# motor-control.net
KiCad netlist of a schematic drawn in Altium Designer
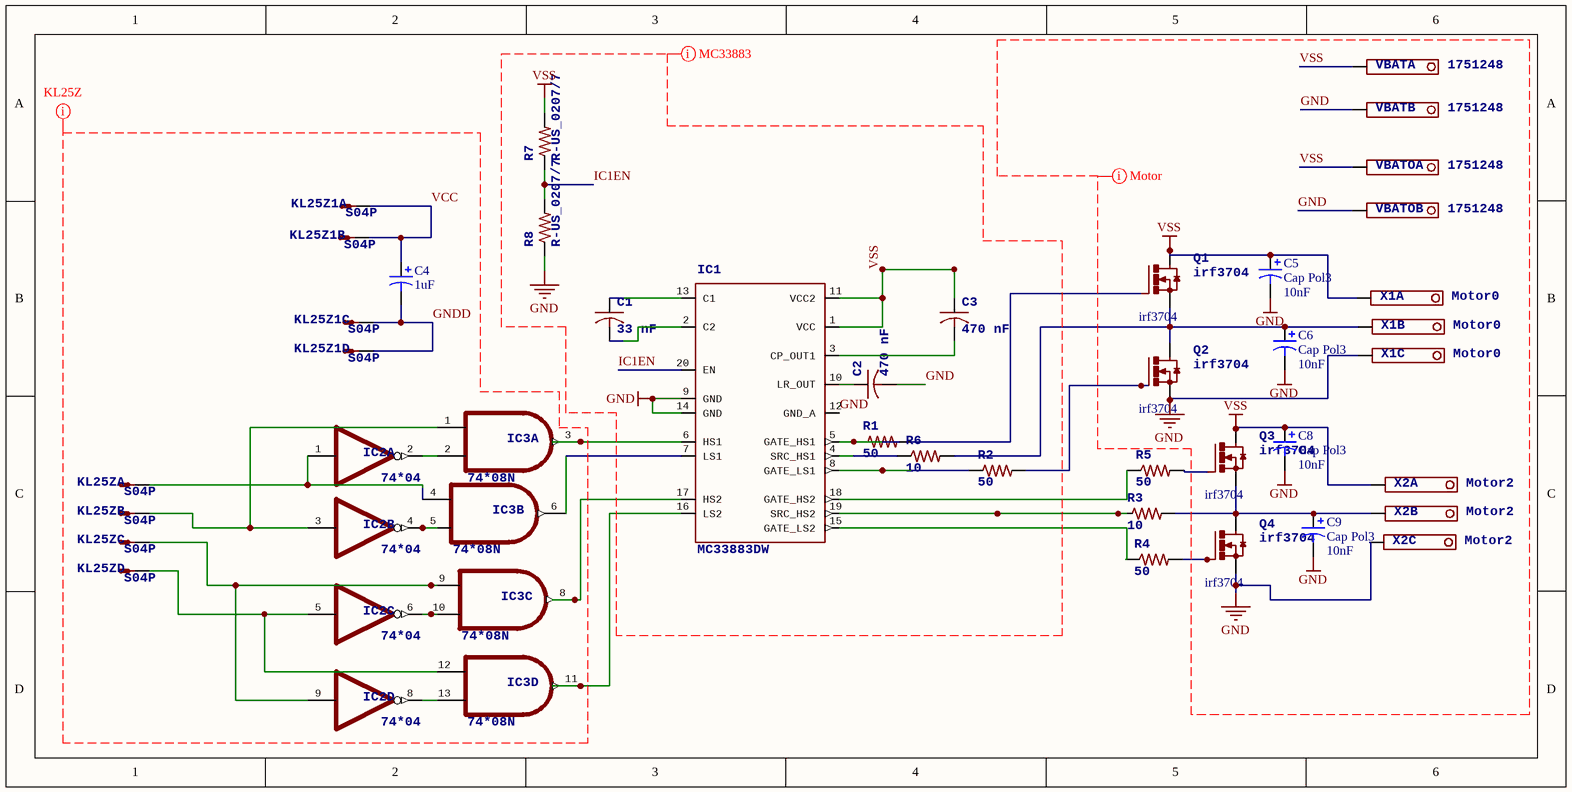
[diagram p0: motor-control.SchDoc]

(export (version "E")
  (design (tool "Eeschema 10.0.6"))
  (components
    (comp (ref "C1")
      (value "33 nF")
      (footprint "C0805")
      (description "<B>CAPACITOR</B>, American symbol")
      (libsource (lib "adafruit") (part "C-USC0805"))
    )
    (comp (ref "C2")
      (value "470 nF")
      (footprint "C0805")
      (description "<B>CAPACITOR</B>, American symbol")
      (libsource (lib "adafruit") (part "C-USC0805"))
    )
    (comp (ref "C3")
      (value "470 nF")
      (footprint "C0805")
      (description "<B>CAPACITOR</B>, American symbol")
      (libsource (lib "adafruit") (part "C-USC0805"))
    )
    (comp (ref "C4")
      (value "1uF")
      (footprint "C0805")
      (description "Polarized Capacitor (Surface Mount)")
      (fields (field (name "PUBLISHER") "Altium Limited"))
      (libsource (lib "Miscellaneous Devices") (part "Cap Pol3"))
    )
    (comp (ref "C5")
      (value "Cap Pol3")
      (footprint "C0805")
      (description "Polarized Capacitor (Surface Mount)")
      (fields (field (name "ALTIUM_VALUE") "10nF") (field (name "PUBLISHER") "Altium Limited"))
      (libsource (lib "Miscellaneous Devices") (part "Cap Pol3"))
    )
    (comp (ref "C6")
      (value "Cap Pol3")
      (footprint "C0805")
      (description "Polarized Capacitor (Surface Mount)")
      (fields (field (name "ALTIUM_VALUE") "10nF") (field (name "PUBLISHER") "Altium Limited"))
      (libsource (lib "Miscellaneous Devices") (part "Cap Pol3"))
    )
    (comp (ref "C8")
      (value "Cap Pol3")
      (footprint "C0805")
      (description "Polarized Capacitor (Surface Mount)")
      (fields (field (name "ALTIUM_VALUE") "10nF") (field (name "PUBLISHER") "Altium Limited"))
      (libsource (lib "Miscellaneous Devices") (part "Cap Pol3"))
    )
    (comp (ref "C9")
      (value "Cap Pol3")
      (footprint "C0805")
      (description "Polarized Capacitor (Surface Mount)")
      (fields (field (name "ALTIUM_VALUE") "10nF") (field (name "PUBLISHER") "Altium Limited"))
      (libsource (lib "Miscellaneous Devices") (part "Cap Pol3"))
    )
    (comp (ref "IC1")
      (value "MC33883DW")
      (footprint "SO20l")
      (description "<b>Full Bridge Pre-Driver</b> 55V<p>\nSource: www.motorola.com/... MC33883.pdf")
      (libsource (lib "motorola-sensor-driver") (part "MC33883DW"))
    )
    (comp (ref "IC2") (value "74*04") (footprint "SO14") (libsource (lib "74xx-us") (part "74*04D")))
    (comp (ref "IC3") (value "74*08N") (footprint "SO14") (libsource (lib "74xx-us") (part "74*08D")))
    (comp (ref "KL25Z")
      (value "S04P")
      (footprint "S04P")
      (description "<b>AMP MT CONNECTOR</b>")
      (libsource (lib "con-amp-mt") (part "S04P"))
    )
    (comp (ref "KL25Z1")
      (value "S04P")
      (footprint "S04P")
      (description "<b>AMP MT CONNECTOR</b>")
      (libsource (lib "con-amp-mt") (part "S04P"))
    )
    (comp (ref "Q1")
      (value "irf3704")
      (footprint "TO220BH")
      (fields (field (name "ID") "irf3704"))
      (libsource (lib "transistor-power") (part "IRF3704-H"))
    )
    (comp (ref "Q2")
      (value "irf3704")
      (footprint "TO220BH")
      (fields (field (name "ID") "irf3704"))
      (libsource (lib "transistor-power") (part "IRF3704-H"))
    )
    (comp (ref "Q3")
      (value "irf3704")
      (footprint "TO220BH")
      (fields (field (name "ID") "irf3704"))
      (libsource (lib "transistor-power") (part "IRF3704-H"))
    )
    (comp (ref "Q4")
      (value "irf3704")
      (footprint "TO220BH")
      (fields (field (name "ID") "irf3704"))
      (libsource (lib "transistor-power") (part "IRF3704-H"))
    )
    (comp (ref "R1")
      (value "50")
      (footprint "M0805")
      (description "<B>RESISTOR</B>, American symbol")
      (libsource (lib "adafruit") (part "R-US_M0805"))
    )
    (comp (ref "R2")
      (value "50")
      (footprint "M0805")
      (description "<B>RESISTOR</B>, American symbol")
      (libsource (lib "adafruit") (part "R-US_M0805"))
    )
    (comp (ref "R3")
      (value "10")
      (footprint "M0805")
      (description "<B>RESISTOR</B>, American symbol")
      (libsource (lib "adafruit") (part "R-US_M0805"))
    )
    (comp (ref "R4")
      (value "50")
      (footprint "M0805")
      (description "<B>RESISTOR</B>, American symbol")
      (libsource (lib "adafruit") (part "R-US_M0805"))
    )
    (comp (ref "R5")
      (value "50")
      (footprint "M0805")
      (description "<B>RESISTOR</B>, American symbol")
      (libsource (lib "adafruit") (part "R-US_M0805"))
    )
    (comp (ref "R6")
      (value "10")
      (footprint "M0805")
      (description "<B>RESISTOR</B>, American symbol")
      (libsource (lib "adafruit") (part "R-US_M0805"))
    )
    (comp (ref "R7")
      (value "R-US_0207/7")
      (footprint "0207/7")
      (description "<B>RESISTOR</B>, American symbol")
      (libsource (lib "adafruit") (part "R-US_0207/7"))
    )
    (comp (ref "R8")
      (value "R-US_0207/7")
      (footprint "0207/7")
      (description "<B>RESISTOR</B>, American symbol")
      (libsource (lib "adafruit") (part "R-US_0207/7"))
    )
    (comp (ref "VBAT") (value "1751248") (footprint "1751248") (libsource (lib "") (part "1751248_1")))
    (comp (ref "VBATO")
      (value "1751248")
      (footprint "1751248")
      (libsource (lib "con-phoenix-350") (part "1751248"))
    )
    (comp (ref "X1")
      (value "Motor0")
      (footprint "1751251")
      (libsource (lib "con-phoenix-350") (part "1751251"))
    )
    (comp (ref "X2")
      (value "Motor2")
      (footprint "1751251")
      (libsource (lib "con-phoenix-350") (part "1751251"))
    )
  )
  (nets
    (net (code "1") (name "/GNDD") (class "Default")
      (node (ref "C4") (pin "2") (pinfunction "2_2") (pintype "passive"))
      (node (ref "KL25Z1") (pin "3") (pinfunction "S_3") (pintype "passive"))
      (node (ref "KL25Z1") (pin "4") (pinfunction "S_4") (pintype "passive"))
    )
    (net (code "2") (name "/IC1EN") (class "Default")
      (node (ref "IC1") (pin "20") (pinfunction "EN_20") (pintype "passive"))
      (node (ref "R7") (pin "1") (pinfunction "1_1") (pintype "passive"))
      (node (ref "R8") (pin "2") (pinfunction "2_2") (pintype "passive"))
    )
    (net (code "3") (name "/VCC") (class "Default")
      (node (ref "C4") (pin "1") (pinfunction "1_1") (pintype "passive"))
      (node (ref "KL25Z1") (pin "1") (pinfunction "S_1") (pintype "passive"))
      (node (ref "KL25Z1") (pin "2") (pinfunction "S_2") (pintype "passive"))
    )
    (net (code "4") (name "GND") (class "Default")
      (node (ref "C2") (pin "2") (pinfunction "2_2") (pintype "passive"))
      (node (ref "C5") (pin "2") (pinfunction "2_2") (pintype "passive"))
      (node (ref "C6") (pin "2") (pinfunction "2_2") (pintype "passive"))
      (node (ref "C8") (pin "2") (pinfunction "2_2") (pintype "passive"))
      (node (ref "C9") (pin "2") (pinfunction "2_2") (pintype "passive"))
      (node (ref "IC1") (pin "12") (pinfunction "GND_A_12") (pintype "power_in"))
      (node (ref "IC1") (pin "14") (pinfunction "GND_14") (pintype "power_in"))
      (node (ref "IC1") (pin "9") (pinfunction "GND_9") (pintype "power_in"))
      (node (ref "Q2") (pin "S") (pinfunction "S_S") (pintype "passive"))
      (node (ref "Q4") (pin "S") (pinfunction "S_S") (pintype "passive"))
      (node (ref "R8") (pin "1") (pinfunction "1_1") (pintype "passive"))
      (node (ref "VBAT") (pin "2") (pinfunction "K_2") (pintype "passive"))
      (node (ref "VBATO") (pin "2") (pinfunction "K_2") (pintype "passive"))
      (node (ref "X1") (pin "3") (pinfunction "K_3") (pintype "passive"))
      (node (ref "X2") (pin "3") (pinfunction "K_3") (pintype "passive"))
    )
    (net (code "5") (name "Net-(IC1-C1)") (class "Default")
      (node (ref "C1") (pin "1") (pinfunction "1_1") (pintype "passive"))
      (node (ref "IC1") (pin "13") (pinfunction "C1_13") (pintype "passive"))
    )
    (net (code "6") (name "Net-(IC1-C2)") (class "Default")
      (node (ref "C1") (pin "2") (pinfunction "2_2") (pintype "passive"))
      (node (ref "IC1") (pin "2") (pinfunction "C2_2") (pintype "passive"))
    )
    (net (code "7") (name "Net-(IC1-CP_OUT1)") (class "Default")
      (node (ref "C3") (pin "2") (pinfunction "2_2") (pintype "passive"))
      (node (ref "IC1") (pin "3") (pinfunction "CP_OUT1_3") (pintype "passive"))
    )
    (net (code "8") (name "Net-(IC1-GATE_HS1)") (class "Default")
      (node (ref "IC1") (pin "5") (pinfunction "GATE_HS1_5") (pintype "output"))
      (node (ref "R1") (pin "1") (pinfunction "1_1") (pintype "passive"))
    )
    (net (code "9") (name "Net-(IC1-GATE_HS2)") (class "Default")
      (node (ref "IC1") (pin "18") (pinfunction "GATE_HS2_18") (pintype "output"))
      (node (ref "R5") (pin "1") (pinfunction "1_1") (pintype "passive"))
    )
    (net (code "10") (name "Net-(IC1-GATE_LS1)") (class "Default")
      (node (ref "IC1") (pin "8") (pinfunction "GATE_LS1_8") (pintype "output"))
      (node (ref "R2") (pin "1") (pinfunction "1_1") (pintype "passive"))
    )
    (net (code "11") (name "Net-(IC1-GATE_LS2)") (class "Default")
      (node (ref "IC1") (pin "15") (pinfunction "GATE_LS2_15") (pintype "output"))
      (node (ref "R4") (pin "1") (pinfunction "1_1") (pintype "passive"))
    )
    (net (code "12") (name "Net-(IC1-HS1)") (class "Default")
      (node (ref "IC1") (pin "6") (pinfunction "HS1_6") (pintype "passive"))
      (node (ref "IC3") (pin "3") (pinfunction "O_3") (pintype "output"))
    )
    (net (code "13") (name "Net-(IC1-HS2)") (class "Default")
      (node (ref "IC1") (pin "17") (pinfunction "HS2_17") (pintype "passive"))
      (node (ref "IC3") (pin "8") (pinfunction "O_8") (pintype "output"))
    )
    (net (code "14") (name "Net-(IC1-LR_OUT)") (class "Default")
      (node (ref "C2") (pin "1") (pinfunction "1_1") (pintype "passive"))
      (node (ref "IC1") (pin "10") (pinfunction "LR_OUT_10") (pintype "passive"))
    )
    (net (code "15") (name "Net-(IC1-LS1)") (class "Default")
      (node (ref "IC1") (pin "7") (pinfunction "LS1_7") (pintype "passive"))
      (node (ref "IC3") (pin "6") (pinfunction "O_6") (pintype "output"))
    )
    (net (code "16") (name "Net-(IC1-LS2)") (class "Default")
      (node (ref "IC1") (pin "16") (pinfunction "LS2_16") (pintype "passive"))
      (node (ref "IC3") (pin "11") (pinfunction "O_11") (pintype "output"))
    )
    (net (code "17") (name "Net-(IC1-SRC_HS1)") (class "Default")
      (node (ref "IC1") (pin "4") (pinfunction "SRC_HS1_4") (pintype "output"))
      (node (ref "R6") (pin "1") (pinfunction "1_1") (pintype "passive"))
    )
    (net (code "18") (name "Net-(IC1-SRC_HS2)") (class "Default")
      (node (ref "IC1") (pin "19") (pinfunction "SRC_HS2_19") (pintype "output"))
      (node (ref "R3") (pin "1") (pinfunction "1_1") (pintype "passive"))
    )
    (net (code "19") (name "Net-(IC2A-I)") (class "Default")
      (node (ref "IC2") (pin "1") (pinfunction "I_1") (pintype "passive"))
      (node (ref "IC3") (pin "4") (pinfunction "I0_4") (pintype "passive"))
      (node (ref "KL25Z") (pin "1") (pinfunction "S_1") (pintype "passive"))
    )
    (net (code "20") (name "Net-(IC2A-O)") (class "Default")
      (node (ref "IC2") (pin "2") (pinfunction "O_2") (pintype "output"))
      (node (ref "IC3") (pin "2") (pinfunction "I1_2") (pintype "passive"))
    )
    (net (code "21") (name "Net-(IC2B-I)") (class "Default")
      (node (ref "IC2") (pin "3") (pinfunction "I_3") (pintype "passive"))
      (node (ref "IC3") (pin "1") (pinfunction "I0_1") (pintype "passive"))
      (node (ref "KL25Z") (pin "2") (pinfunction "S_2") (pintype "passive"))
    )
    (net (code "22") (name "Net-(IC2B-O)") (class "Default")
      (node (ref "IC2") (pin "4") (pinfunction "O_4") (pintype "output"))
      (node (ref "IC3") (pin "5") (pinfunction "I1_5") (pintype "passive"))
    )
    (net (code "23") (name "Net-(IC2C-I)") (class "Default")
      (node (ref "IC2") (pin "5") (pinfunction "I_5") (pintype "passive"))
      (node (ref "IC3") (pin "12") (pinfunction "I0_12") (pintype "passive"))
      (node (ref "KL25Z") (pin "4") (pinfunction "S_4") (pintype "passive"))
    )
    (net (code "24") (name "Net-(IC2C-O)") (class "Default")
      (node (ref "IC2") (pin "6") (pinfunction "O_6") (pintype "output"))
      (node (ref "IC3") (pin "10") (pinfunction "I1_10") (pintype "passive"))
    )
    (net (code "25") (name "Net-(IC2D-I)") (class "Default")
      (node (ref "IC2") (pin "9") (pinfunction "I_9") (pintype "passive"))
      (node (ref "IC3") (pin "9") (pinfunction "I0_9") (pintype "passive"))
      (node (ref "KL25Z") (pin "3") (pinfunction "S_3") (pintype "passive"))
    )
    (net (code "26") (name "Net-(IC2D-O)") (class "Default")
      (node (ref "IC2") (pin "8") (pinfunction "O_8") (pintype "output"))
      (node (ref "IC3") (pin "13") (pinfunction "I1_13") (pintype "passive"))
    )
    (net (code "27") (name "Net-(Q1-PadG)") (class "Default")
      (node (ref "Q1") (pin "G") (pinfunction "G_G") (pintype "passive"))
      (node (ref "R1") (pin "2") (pinfunction "2_2") (pintype "passive"))
    )
    (net (code "28") (name "Net-(Q2-PadG)") (class "Default")
      (node (ref "Q2") (pin "G") (pinfunction "G_G") (pintype "passive"))
      (node (ref "R2") (pin "2") (pinfunction "2_2") (pintype "passive"))
    )
    (net (code "29") (name "Net-(Q3-PadG)") (class "Default")
      (node (ref "Q3") (pin "G") (pinfunction "G_G") (pintype "passive"))
      (node (ref "R5") (pin "2") (pinfunction "2_2") (pintype "passive"))
    )
    (net (code "30") (name "Net-(Q4-PadG)") (class "Default")
      (node (ref "Q4") (pin "G") (pinfunction "G_G") (pintype "passive"))
      (node (ref "R4") (pin "2") (pinfunction "2_2") (pintype "passive"))
    )
    (net (code "31") (name "Net-(X1B-K)") (class "Default")
      (node (ref "C6") (pin "1") (pinfunction "1_1") (pintype "passive"))
      (node (ref "Q1") (pin "S") (pinfunction "S_S") (pintype "passive"))
      (node (ref "Q2") (pin "D") (pinfunction "D_D") (pintype "passive"))
      (node (ref "R6") (pin "2") (pinfunction "2_2") (pintype "passive"))
      (node (ref "X1") (pin "2") (pinfunction "K_2") (pintype "passive"))
    )
    (net (code "32") (name "Net-(X2B-K)") (class "Default")
      (node (ref "C9") (pin "1") (pinfunction "1_1") (pintype "passive"))
      (node (ref "Q3") (pin "S") (pinfunction "S_S") (pintype "passive"))
      (node (ref "Q4") (pin "D") (pinfunction "D_D") (pintype "passive"))
      (node (ref "R3") (pin "2") (pinfunction "2_2") (pintype "passive"))
      (node (ref "X2") (pin "2") (pinfunction "K_2") (pintype "passive"))
    )
    (net (code "33") (name "VSS") (class "Default")
      (node (ref "C3") (pin "1") (pinfunction "1_1") (pintype "passive"))
      (node (ref "C5") (pin "1") (pinfunction "1_1") (pintype "passive"))
      (node (ref "C8") (pin "1") (pinfunction "1_1") (pintype "passive"))
      (node (ref "IC1") (pin "1") (pinfunction "VCC_1") (pintype "power_in"))
      (node (ref "IC1") (pin "11") (pinfunction "VCC2_11") (pintype "power_in"))
      (node (ref "Q1") (pin "D") (pinfunction "D_D") (pintype "passive"))
      (node (ref "Q3") (pin "D") (pinfunction "D_D") (pintype "passive"))
      (node (ref "R7") (pin "2") (pinfunction "2_2") (pintype "passive"))
      (node (ref "VBAT") (pin "1") (pinfunction "K_1") (pintype "passive"))
      (node (ref "VBATO") (pin "1") (pinfunction "K_1") (pintype "passive"))
      (node (ref "X1") (pin "1") (pinfunction "K_1") (pintype "passive"))
      (node (ref "X2") (pin "1") (pinfunction "K_1") (pintype "passive"))
    )
  )
)
